# MPU6050.net
KiCad netlist of a schematic drawn in EasyEDA Pro
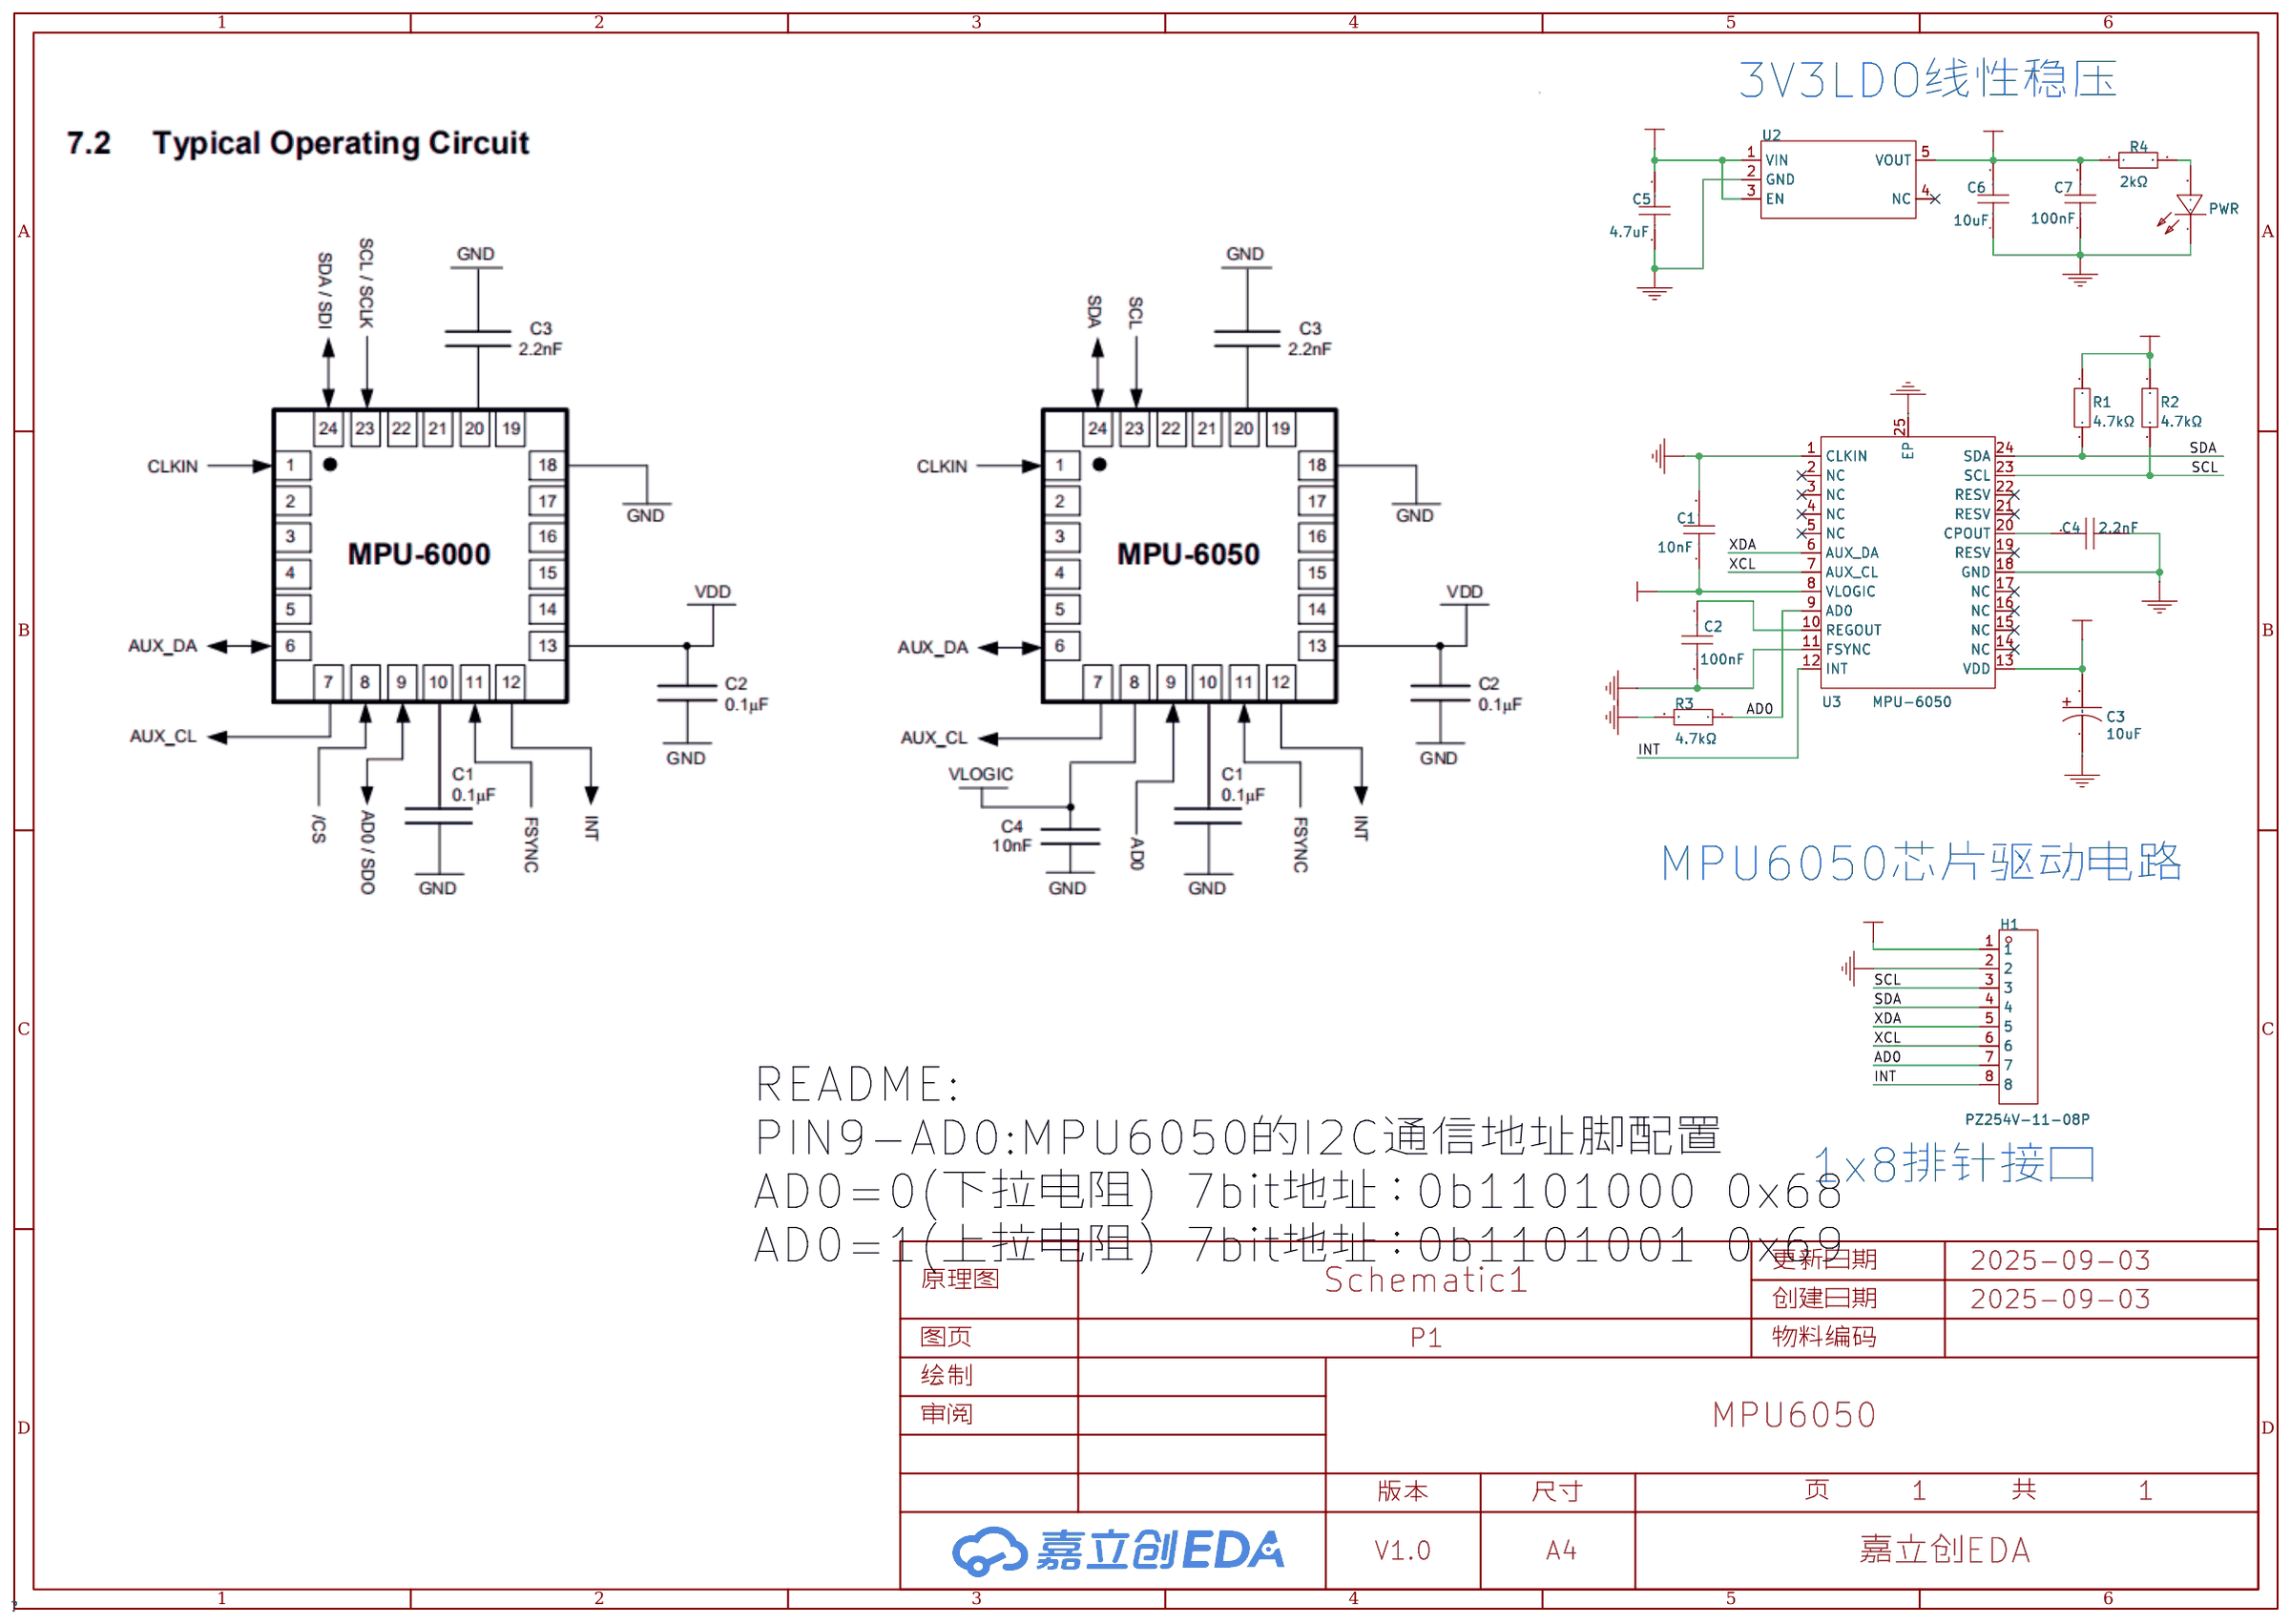
[diagram p0: schematic sheet]

(export (version "E")
  (design (tool "Eeschema 10.0.6"))
  (components
    (comp (ref "C1")
      (value "10nF")
      (footprint "easyedapro:C0402")
      (fields (field (name "Manufacturer") "SAMSUNG(三星)"))
      (libsource (lib "easyedapro") (part "10nF/4v"))
    )
    (comp (ref "C2")
      (value "100nF")
      (footprint "easyedapro:C0402")
      (fields (field (name "Manufacturer") "SAMSUNG(三星)"))
      (libsource (lib "easyedapro") (part "0.1uF/2v/104"))
    )
    (comp (ref "C3")
      (value "10uF")
      (footprint "easyedapro:CAP-SMD_L3.2-W1.6")
      (fields (field (name "Manufacturer Part") "TPSA106K016R1000") (field (name "Manufacturer") "AVX"))
      (libsource (lib "easyedapro") (part "0.1uF/4v/104"))
    )
    (comp (ref "C4")
      (value "2.2nF")
      (footprint "easyedapro:C0402")
      (fields (field (name "Manufacturer") "FH(风华)"))
      (libsource (lib "easyedapro") (part "2.2nF/50V"))
    )
    (comp (ref "C5")
      (value "4.7uF")
      (footprint "easyedapro:C0402")
      (fields (field (name "Manufacturer") "SAMSUNG(三星)"))
      (libsource (lib "easyedapro") (part "4.7uF"))
    )
    (comp (ref "C6")
      (value "10uF")
      (footprint "easyedapro:C0402")
      (fields (field (name "Manufacturer") "SAMSUNG(三星)"))
      (libsource (lib "easyedapro") (part "10uF"))
    )
    (comp (ref "C7")
      (value "100nF")
      (footprint "easyedapro:C0402")
      (fields (field (name "Manufacturer") "SAMSUNG(三星)"))
      (libsource (lib "easyedapro") (part "0.1uF"))
    )
    (comp (ref "H1")
      (value "PZ254V-11-08P")
      (footprint "easyedapro:HDR-TH_8P-P2.54-V-M")
      (fields (field (name "Manufacturer") "XFCN(兴飞)"))
      (libsource (lib "easyedapro") (part "PZ254V-11-08P"))
    )
    (comp (ref "PWR")
      (value "LTST-C193KRKT-5A")
      (footprint "easyedapro:LED0603-RD")
      (fields (field (name "Manufacturer") "LITEON(光宝)"))
      (libsource (lib "easyedapro") (part "LTST-C193KRKT-5A"))
    )
    (comp (ref "R1")
      (value "4.7kΩ")
      (footprint "easyedapro:R0402")
      (description "电阻类型:厚膜电阻;阻值:4.7kΩ;精度:±1%;功率:62.5mW;最大工作电压:50V;温度系数:±100ppm/°C;")
      (fields
        (field (name "Manufacturer Part") "0402WGF4701TCE")
        (field (name "Manufacturer") "UNI-ROYAL(厚声)")
      )
      (libsource (lib "easyedapro") (part "0402WGF4701TCE"))
    )
    (comp (ref "R2")
      (value "4.7kΩ")
      (footprint "easyedapro:R0402")
      (description "电阻类型:厚膜电阻;阻值:4.7kΩ;精度:±1%;功率:62.5mW;最大工作电压:50V;温度系数:±100ppm/°C;")
      (fields
        (field (name "Manufacturer Part") "0402WGF4701TCE")
        (field (name "Manufacturer") "UNI-ROYAL(厚声)")
      )
      (libsource (lib "easyedapro") (part "0402WGF4701TCE"))
    )
    (comp (ref "R3")
      (value "4.7kΩ")
      (footprint "easyedapro:R0402")
      (description "电阻类型:厚膜电阻;阻值:4.7kΩ;精度:±1%;功率:62.5mW;最大工作电压:50V;温度系数:±100ppm/°C;")
      (fields
        (field (name "Manufacturer Part") "0402WGF4701TCE")
        (field (name "Manufacturer") "UNI-ROYAL(厚声)")
      )
      (libsource (lib "easyedapro") (part "0402WGF4701TCE"))
    )
    (comp (ref "R4")
      (value "2kΩ")
      (footprint "easyedapro:R0402")
      (description "电阻类型:厚膜电阻;阻值:2kΩ;精度:±1%;功率:62.5mW;最大工作电压:50V;温度系数:±100ppm/°C;")
      (fields
        (field (name "Manufacturer Part") "0402WGF2001TCE")
        (field (name "Manufacturer") "UNI-ROYAL(厚声)")
      )
      (libsource (lib "easyedapro") (part "0402WGF2001TCE"))
    )
    (comp (ref "U2")
      (value "HX9193-33GB")
      (footprint "easyedapro:SOT-23-5_L3.0-W1.7-P0.95-LS2.8-BR")
      (fields (field (name "Manufacturer") "hengjiaxing"))
      (libsource (lib "easyedapro") (part "HX9193-33GB"))
    )
    (comp (ref "U3")
      (value "MPU-6050")
      (footprint "easyedapro:QFN-24_L4.0-W4.0-P0.50-BL-EP2.7")
      (description "传感器类型:加速度计陀螺仪;")
      (fields (field (name "Manufacturer") "TDK InvenSense(应美盛)"))
      (libsource (lib "easyedapro") (part "MPU-6050_C24112"))
    )
  )
  (nets
    (net (code "1") (name "/AD0") (class "Default")
      (node (ref "H1") (pin "7") (pinfunction "7_7") (pintype "unspecified"))
      (node (ref "R3") (pin "1") (pinfunction "1_1") (pintype "input"))
      (node (ref "U3") (pin "9") (pinfunction "AD0_9") (pintype "unspecified"))
    )
    (net (code "2") (name "/INT") (class "Default")
      (node (ref "H1") (pin "8") (pinfunction "8_8") (pintype "unspecified"))
      (node (ref "U3") (pin "12") (pinfunction "INT_12") (pintype "unspecified"))
    )
    (net (code "3") (name "/SCL") (class "Default")
      (node (ref "H1") (pin "3") (pinfunction "3_3") (pintype "unspecified"))
      (node (ref "R2") (pin "1") (pinfunction "1_1") (pintype "input"))
      (node (ref "U3") (pin "23") (pinfunction "SCL_23") (pintype "unspecified"))
    )
    (net (code "4") (name "/SDA") (class "Default")
      (node (ref "H1") (pin "4") (pinfunction "4_4") (pintype "unspecified"))
      (node (ref "R1") (pin "1") (pinfunction "1_1") (pintype "input"))
      (node (ref "U3") (pin "24") (pinfunction "SDA_24") (pintype "unspecified"))
    )
    (net (code "5") (name "/XCL") (class "Default")
      (node (ref "H1") (pin "6") (pinfunction "6_6") (pintype "unspecified"))
      (node (ref "U3") (pin "7") (pinfunction "AUX_CL_7") (pintype "unspecified"))
    )
    (net (code "6") (name "/XDA") (class "Default")
      (node (ref "H1") (pin "5") (pinfunction "5_5") (pintype "unspecified"))
      (node (ref "U3") (pin "6") (pinfunction "AUX_DA_6") (pintype "unspecified"))
    )
    (net (code "7") (name "3V3") (class "Default")
      (node (ref "C1") (pin "1") (pinfunction "1_1") (pintype "unspecified"))
      (node (ref "C3") (pin "1") (pinfunction "1_1") (pintype "unspecified"))
      (node (ref "C6") (pin "2") (pinfunction "2_2") (pintype "unspecified"))
      (node (ref "C7") (pin "2") (pinfunction "2_2") (pintype "unspecified"))
      (node (ref "R1") (pin "2") (pinfunction "2_2") (pintype "input"))
      (node (ref "R2") (pin "2") (pinfunction "2_2") (pintype "input"))
      (node (ref "R4") (pin "1") (pinfunction "1_1") (pintype "input"))
      (node (ref "U2") (pin "5") (pinfunction "VOUT_5") (pintype "unspecified"))
      (node (ref "U3") (pin "13") (pinfunction "VDD_13") (pintype "unspecified"))
      (node (ref "U3") (pin "8") (pinfunction "VLOGIC_8") (pintype "unspecified"))
    )
    (net (code "8") (name "GND") (class "Default")
      (node (ref "C1") (pin "2") (pinfunction "2_2") (pintype "unspecified"))
      (node (ref "C2") (pin "2") (pinfunction "2_2") (pintype "unspecified"))
      (node (ref "C3") (pin "2") (pinfunction "2_2") (pintype "unspecified"))
      (node (ref "C4") (pin "1") (pinfunction "1_1") (pintype "unspecified"))
      (node (ref "C5") (pin "1") (pinfunction "1_1") (pintype "unspecified"))
      (node (ref "C6") (pin "1") (pinfunction "1_1") (pintype "unspecified"))
      (node (ref "C7") (pin "1") (pinfunction "1_1") (pintype "unspecified"))
      (node (ref "H1") (pin "2") (pinfunction "2_2") (pintype "unspecified"))
      (node (ref "PWR") (pin "1") (pinfunction "K_1") (pintype "unspecified"))
      (node (ref "R3") (pin "2") (pinfunction "2_2") (pintype "input"))
      (node (ref "U2") (pin "2") (pinfunction "GND_2") (pintype "unspecified"))
      (node (ref "U3") (pin "1") (pinfunction "CLKIN_1") (pintype "unspecified"))
      (node (ref "U3") (pin "11") (pinfunction "FSYNC_11") (pintype "unspecified"))
      (node (ref "U3") (pin "18") (pinfunction "GND_18") (pintype "unspecified"))
      (node (ref "U3") (pin "25") (pinfunction "EP_25") (pintype "unspecified"))
    )
    (net (code "9") (name "MAX6V_IN") (class "Default")
      (node (ref "C5") (pin "2") (pinfunction "2_2") (pintype "unspecified"))
      (node (ref "H1") (pin "1") (pinfunction "1_1") (pintype "unspecified"))
      (node (ref "U2") (pin "1") (pinfunction "VIN_1") (pintype "unspecified"))
      (node (ref "U2") (pin "3") (pinfunction "EN_3") (pintype "unspecified"))
    )
    (net (code "10") (name "Net-(PWR-A)") (class "Default")
      (node (ref "PWR") (pin "2") (pinfunction "A_2") (pintype "unspecified"))
      (node (ref "R4") (pin "2") (pinfunction "2_2") (pintype "input"))
    )
    (net (code "11") (name "Net-(U3-CPOUT)") (class "Default")
      (node (ref "C4") (pin "2") (pinfunction "2_2") (pintype "unspecified"))
      (node (ref "U3") (pin "20") (pinfunction "CPOUT_20") (pintype "unspecified"))
    )
    (net (code "12") (name "Net-(U3-REGOUT)") (class "Default")
      (node (ref "C2") (pin "1") (pinfunction "1_1") (pintype "unspecified"))
      (node (ref "U3") (pin "10") (pinfunction "REGOUT_10") (pintype "unspecified"))
    )
    (net (code "13") (name "unconnected-(U2-NC-Pad4)") (class "Default")
      (node (ref "U2") (pin "4") (pinfunction "NC_4") (pintype "unspecified+no_connect"))
    )
    (net (code "14") (name "unconnected-(U3-NC-Pad2)") (class "Default")
      (node (ref "U3") (pin "2") (pinfunction "NC_2") (pintype "unspecified+no_connect"))
    )
    (net (code "15") (name "unconnected-(U3-NC-Pad3)") (class "Default")
      (node (ref "U3") (pin "3") (pinfunction "NC_3") (pintype "unspecified+no_connect"))
    )
    (net (code "16") (name "unconnected-(U3-NC-Pad4)") (class "Default")
      (node (ref "U3") (pin "4") (pinfunction "NC_4") (pintype "unspecified+no_connect"))
    )
    (net (code "17") (name "unconnected-(U3-NC-Pad5)") (class "Default")
      (node (ref "U3") (pin "5") (pinfunction "NC_5") (pintype "unspecified+no_connect"))
    )
    (net (code "18") (name "unconnected-(U3-NC-Pad14)") (class "Default")
      (node (ref "U3") (pin "14") (pinfunction "NC_14") (pintype "unspecified+no_connect"))
    )
    (net (code "19") (name "unconnected-(U3-NC-Pad15)") (class "Default")
      (node (ref "U3") (pin "15") (pinfunction "NC_15") (pintype "unspecified+no_connect"))
    )
    (net (code "20") (name "unconnected-(U3-NC-Pad16)") (class "Default")
      (node (ref "U3") (pin "16") (pinfunction "NC_16") (pintype "unspecified+no_connect"))
    )
    (net (code "21") (name "unconnected-(U3-NC-Pad17)") (class "Default")
      (node (ref "U3") (pin "17") (pinfunction "NC_17") (pintype "unspecified+no_connect"))
    )
    (net (code "22") (name "unconnected-(U3-RESV-Pad19)") (class "Default")
      (node (ref "U3") (pin "19") (pinfunction "RESV_19") (pintype "unspecified+no_connect"))
    )
    (net (code "23") (name "unconnected-(U3-RESV-Pad21)") (class "Default")
      (node (ref "U3") (pin "21") (pinfunction "RESV_21") (pintype "unspecified+no_connect"))
    )
    (net (code "24") (name "unconnected-(U3-RESV-Pad22)") (class "Default")
      (node (ref "U3") (pin "22") (pinfunction "RESV_22") (pintype "unspecified+no_connect"))
    )
  )
)
